# Output_terminals.net
KiCad netlist of a schematic drawn in Altium Designer
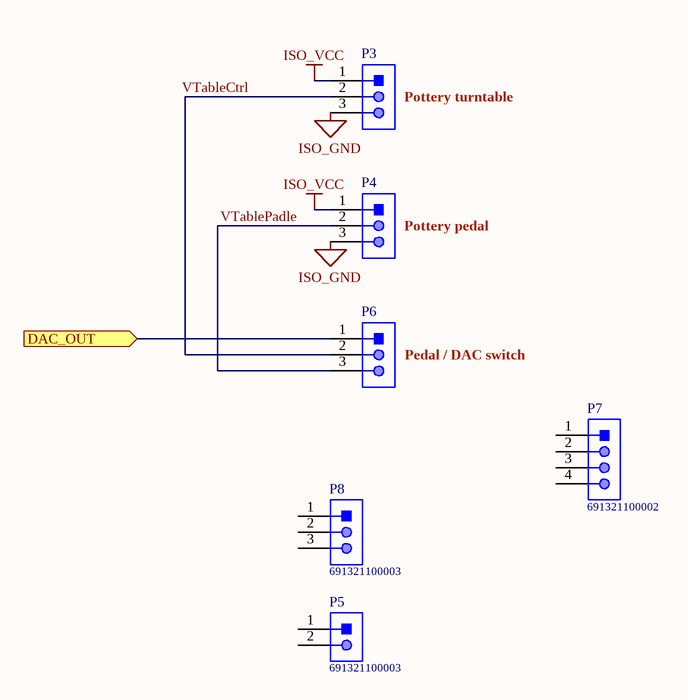
[diagram p0: Output terminals.SchDoc]

(export (version "E")
  (design (tool "Eeschema 10.0.6"))
  (components
    (comp (ref "P3")
      (value "691321100003")
      (footprint "691321100003")
      (description "Serie 3211 - 3.50mm Vertical PCB Header WR-TBL, 3 pin")
      (fields (field (name "MANUFACTURER") "Wurth Elektronik") (field (name "PUBLISHER") "WurthElektronik"))
      (libsource (lib "Altium Content Vault") (part "WE-CN-1P-M-R3"))
    )
    (comp (ref "P4")
      (value "691321100002")
      (footprint "691321100003")
      (description "Serie 3211 - 3.50mm Vertical PCB Header WR-TBL, 3 pin")
      (fields
        (field (name "PART NUMBER") "691321100003")
        (field (name "MANUFACTURER") "Wurth Elektronik")
        (field (name "PUBLISHER") "WurthElektronik")
      )
      (libsource (lib "Altium Content Vault") (part "WE-CN-1P-M-R3"))
    )
    (comp (ref "P5")
      (value "691321100003")
      (footprint "691321100002")
      (description "Serie 3211 - 3.50mm Vertical PCB Header WR-TBL, 2 pin")
      (fields
        (field (name "PART NUMBER") "691321100002")
        (field (name "MANUFACTURER") "Wurth Elektronik")
        (field (name "PUBLISHER") "WurthElektronik")
      )
      (libsource (lib "Altium Content Vault") (part "WE-CN-1P-M-R2"))
    )
    (comp (ref "P6")
      (value "691321100002")
      (footprint "691321100003")
      (description "Serie 3211 - 3.50mm Vertical PCB Header WR-TBL, 3 pin")
      (fields
        (field (name "PART NUMBER") "691321100003")
        (field (name "MANUFACTURER") "Wurth Elektronik")
        (field (name "PUBLISHER") "WurthElektronik")
      )
      (libsource (lib "Altium Content Vault") (part "WE-CN-1P-M-R3"))
    )
    (comp (ref "P7")
      (value "691321100002")
      (footprint "691321100004")
      (description "Serie 3211 - 3.50mm Vertical PCB Header WR-TBL, 4 pin")
      (fields
        (field (name "MANUFACTURER") "Wurth Elektronik")
        (field (name "PART NUMBER") "691321100004")
        (field (name "PUBLISHER") "WurthElektronik")
      )
      (libsource (lib "Altium Content Vault") (part "WE-CN-1P-M-R4"))
    )
    (comp (ref "P8")
      (value "691321100003")
      (footprint "691321100003")
      (description "Serie 3211 - 3.50mm Vertical PCB Header WR-TBL, 3 pin")
      (fields (field (name "MANUFACTURER") "Wurth Elektronik") (field (name "PUBLISHER") "WurthElektronik"))
      (libsource (lib "Altium Content Vault") (part "WE-CN-1P-M-R3"))
    )
  )
  (nets
    (net (code "1") (name "/DAC_OUT") (class "Default")
      (node (ref "P6") (pin "1") (pinfunction "1_1") (pintype "passive"))
    )
    (net (code "2") (name "/VTableCtrl") (class "Default")
      (node (ref "P3") (pin "2") (pinfunction "2_2") (pintype "passive"))
      (node (ref "P6") (pin "2") (pinfunction "2_2") (pintype "passive"))
    )
    (net (code "3") (name "/VTablePadle") (class "Default")
      (node (ref "P4") (pin "2") (pinfunction "2_2") (pintype "passive"))
      (node (ref "P6") (pin "3") (pinfunction "3_3") (pintype "passive"))
    )
    (net (code "4") (name "ISO_GND") (class "Default")
      (node (ref "P3") (pin "3") (pinfunction "3_3") (pintype "passive"))
      (node (ref "P4") (pin "3") (pinfunction "3_3") (pintype "passive"))
    )
    (net (code "5") (name "ISO_VCC") (class "Default")
      (node (ref "P3") (pin "1") (pinfunction "1_1") (pintype "passive"))
      (node (ref "P4") (pin "1") (pinfunction "1_1") (pintype "passive"))
    )
    (net (code "6") (name "unconnected-(P5-Pad1)") (class "Default")
      (node (ref "P5") (pin "1") (pinfunction "1_1") (pintype "passive"))
    )
    (net (code "7") (name "unconnected-(P5-Pad2)") (class "Default")
      (node (ref "P5") (pin "2") (pinfunction "2_2") (pintype "passive"))
    )
    (net (code "8") (name "unconnected-(P7-Pad1)") (class "Default")
      (node (ref "P7") (pin "1") (pinfunction "1_1") (pintype "passive"))
    )
    (net (code "9") (name "unconnected-(P7-Pad2)") (class "Default")
      (node (ref "P7") (pin "2") (pinfunction "2_2") (pintype "passive"))
    )
    (net (code "10") (name "unconnected-(P7-Pad3)") (class "Default")
      (node (ref "P7") (pin "3") (pinfunction "3_3") (pintype "passive"))
    )
    (net (code "11") (name "unconnected-(P7-Pad4)") (class "Default")
      (node (ref "P7") (pin "4") (pinfunction "4_4") (pintype "passive"))
    )
    (net (code "12") (name "unconnected-(P8-Pad1)") (class "Default")
      (node (ref "P8") (pin "1") (pinfunction "1_1") (pintype "passive"))
    )
    (net (code "13") (name "unconnected-(P8-Pad2)") (class "Default")
      (node (ref "P8") (pin "2") (pinfunction "2_2") (pintype "passive"))
    )
    (net (code "14") (name "unconnected-(P8-Pad3)") (class "Default")
      (node (ref "P8") (pin "3") (pinfunction "3_3") (pintype "passive"))
    )
  )
)
